# TopSheet.net
KiCad netlist of a schematic drawn in Altium Designer
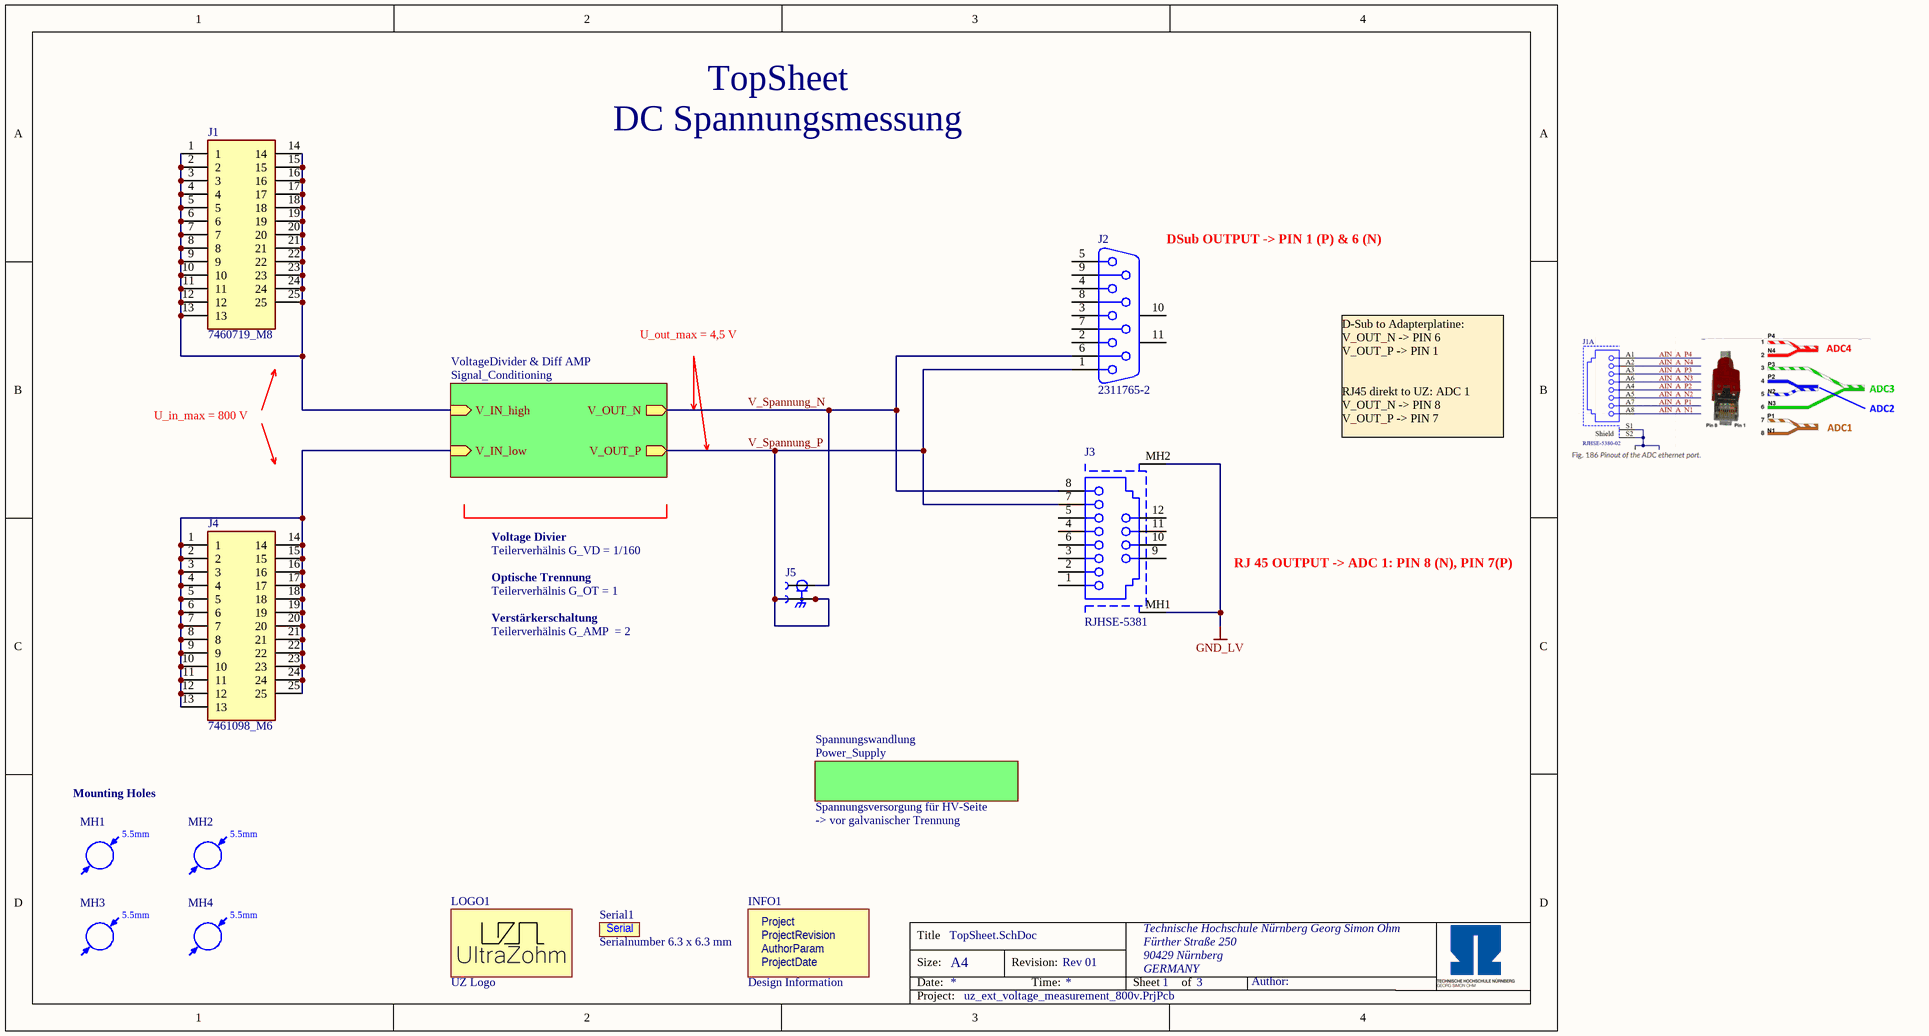
[diagram p0: TopSheet.SchDoc]

(export (version "E")
  (design (tool "Eeschema 10.0.6"))
  (components
    (comp (ref "INFO1")
      (value "Design Information")
      (footprint "Design_info")
      (description "Design InformationS")
      (fields (field (name "MANUFACTURER") "UltraZohm") (field (name "CREATED FROM") "MGremer"))
      (libsource (lib "user") (part "Design_info"))
    )
    (comp (ref "J1")
      (value "7460719_M8")
      (footprint "eigene_lib_alt:7460719")
      (description "Connector")
      (fields
        (field (name "MANUFACTURER_PART_NUMBER") "7460719")
        (field (name "MOUSER PART NUMBER") "710-7460719")
      )
      (libsource (lib "SamacSys") (part "7460719_M8"))
    )
    (comp (ref "J2")
      (value "2311765-2")
      (footprint "2311765-2:2311765-2")
      (description "Connector D-Sub 9 Pin Female")
      (libsource (lib "2311765-2") (part "2311765-2"))
    )
    (comp (ref "J3")
      (value "RJHSE-5381")
      (footprint "eigene_lib_alt:RJHSE-5381")
      (description "Connector Ethernet R/A RJ45 SHIELDED 8 CONT Y/G LEDS")
      (libsource (lib "eigene_lib_alt") (part "RJHSE-5381"))
    )
    (comp (ref "J4")
      (value "7461098_M6")
      (footprint "eigene_lib_alt:7461098")
      (description "Connector")
      (fields
        (field (name "MANUFACTURER_PART_NUMBER") "7461098")
        (field (name "MOUSER PART NUMBER") "710-7461098")
      )
      (libsource (lib "eigene_lib_alt") (part "7461098_M6"))
    )
    (comp (ref "J5")
      (value "BNC5-J-P-GN-ST-TH2D_new")
      (footprint "eigene_lib_alt:BNC5-J-P-GN-ST-TH2D_new")
      (description "BNC Connector")
      (libsource (lib "SamacSys") (part "BNC5-J-P-GN-ST-TH2D_new"))
    )
    (comp (ref "LOGO1")
      (value "UZ Logo")
      (footprint "UZ_Logo_small")
      (fields
        (field (name "MANUFACTURER PART NUMBER") "Logo small")
        (field (name "MANUFACTURER") "UltraZohm")
        (field (name "CREATED") "Jan2021_Liegmann")
        (field (name "CREATED FROM") "MGremer")
      )
      (libsource (lib "user") (part "UZ Logo"))
    )
    (comp (ref "MH1")
      (value "Mounting_Hole_M5")
      (footprint "Mounting_Hole_M5:Mounting Hole (M5)")
      (description "Mounting Hole")
      (libsource (lib "Mounting_Hole_M5") (part "Mounting_Hole_M5"))
    )
    (comp (ref "MH2")
      (value "Mounting_Hole_M5")
      (footprint "Mounting_Hole_M5:Mounting Hole (M5)")
      (description "Mounting Hole")
      (libsource (lib "Mounting_Hole_M5") (part "Mounting_Hole_M5"))
    )
    (comp (ref "MH3")
      (value "Mounting_Hole_M5")
      (footprint "Mounting_Hole_M5:Mounting Hole (M5)")
      (description "Mounting Hole")
      (libsource (lib "Mounting_Hole_M5") (part "Mounting_Hole_M5"))
    )
    (comp (ref "MH4")
      (value "Mounting_Hole_M5")
      (footprint "Mounting_Hole_M5:Mounting Hole (M5)")
      (description "Mounting Hole")
      (libsource (lib "Mounting_Hole_M5") (part "Mounting_Hole_M5"))
    )
    (comp (ref "Serial1")
      (value "Serialnumber 6.3 x 6.3 mm")
      (footprint "SERIAL_6.3X6.3MM")
      (description "Serial Number")
      (fields
        (field (name "MANUFACTURER") "UltraZohm")
        (field (name "CREATED") "2018_09_18_AGeiger")
        (field (name "CREATED FROM") "MGremer")
      )
      (libsource (lib "user") (part "SerialNumber"))
    )
  )
  (nets
    (net (code "1") (name "/V_IN_high") (class "Default")
      (node (ref "J1") (pin "1") (pinfunction "1_1") (pintype "passive"))
      (node (ref "J1") (pin "10") (pinfunction "10_10") (pintype "passive"))
      (node (ref "J1") (pin "11") (pinfunction "11_11") (pintype "passive"))
      (node (ref "J1") (pin "12") (pinfunction "12_12") (pintype "passive"))
      (node (ref "J1") (pin "13") (pinfunction "13_13") (pintype "passive"))
      (node (ref "J1") (pin "14") (pinfunction "14_14") (pintype "passive"))
      (node (ref "J1") (pin "15") (pinfunction "15_15") (pintype "passive"))
      (node (ref "J1") (pin "16") (pinfunction "16_16") (pintype "passive"))
      (node (ref "J1") (pin "17") (pinfunction "17_17") (pintype "passive"))
      (node (ref "J1") (pin "18") (pinfunction "18_18") (pintype "passive"))
      (node (ref "J1") (pin "19") (pinfunction "19_19") (pintype "passive"))
      (node (ref "J1") (pin "2") (pinfunction "2_2") (pintype "passive"))
      (node (ref "J1") (pin "20") (pinfunction "20_20") (pintype "passive"))
      (node (ref "J1") (pin "21") (pinfunction "21_21") (pintype "passive"))
      (node (ref "J1") (pin "22") (pinfunction "22_22") (pintype "passive"))
      (node (ref "J1") (pin "23") (pinfunction "23_23") (pintype "passive"))
      (node (ref "J1") (pin "24") (pinfunction "24_24") (pintype "passive"))
      (node (ref "J1") (pin "25") (pinfunction "25_25") (pintype "passive"))
      (node (ref "J1") (pin "3") (pinfunction "3_3") (pintype "passive"))
      (node (ref "J1") (pin "4") (pinfunction "4_4") (pintype "passive"))
      (node (ref "J1") (pin "5") (pinfunction "5_5") (pintype "passive"))
      (node (ref "J1") (pin "6") (pinfunction "6_6") (pintype "passive"))
      (node (ref "J1") (pin "7") (pinfunction "7_7") (pintype "passive"))
      (node (ref "J1") (pin "8") (pinfunction "8_8") (pintype "passive"))
      (node (ref "J1") (pin "9") (pinfunction "9_9") (pintype "passive"))
    )
    (net (code "2") (name "/V_IN_low") (class "Default")
      (node (ref "J4") (pin "1") (pinfunction "1_1") (pintype "passive"))
      (node (ref "J4") (pin "10") (pinfunction "10_10") (pintype "passive"))
      (node (ref "J4") (pin "11") (pinfunction "11_11") (pintype "passive"))
      (node (ref "J4") (pin "12") (pinfunction "12_12") (pintype "passive"))
      (node (ref "J4") (pin "13") (pinfunction "13_13") (pintype "passive"))
      (node (ref "J4") (pin "14") (pinfunction "14_14") (pintype "passive"))
      (node (ref "J4") (pin "15") (pinfunction "15_15") (pintype "passive"))
      (node (ref "J4") (pin "16") (pinfunction "16_16") (pintype "passive"))
      (node (ref "J4") (pin "17") (pinfunction "17_17") (pintype "passive"))
      (node (ref "J4") (pin "18") (pinfunction "18_18") (pintype "passive"))
      (node (ref "J4") (pin "19") (pinfunction "19_19") (pintype "passive"))
      (node (ref "J4") (pin "2") (pinfunction "2_2") (pintype "passive"))
      (node (ref "J4") (pin "20") (pinfunction "20_20") (pintype "passive"))
      (node (ref "J4") (pin "21") (pinfunction "21_21") (pintype "passive"))
      (node (ref "J4") (pin "22") (pinfunction "22_22") (pintype "passive"))
      (node (ref "J4") (pin "23") (pinfunction "23_23") (pintype "passive"))
      (node (ref "J4") (pin "24") (pinfunction "24_24") (pintype "passive"))
      (node (ref "J4") (pin "25") (pinfunction "25_25") (pintype "passive"))
      (node (ref "J4") (pin "3") (pinfunction "3_3") (pintype "passive"))
      (node (ref "J4") (pin "4") (pinfunction "4_4") (pintype "passive"))
      (node (ref "J4") (pin "5") (pinfunction "5_5") (pintype "passive"))
      (node (ref "J4") (pin "6") (pinfunction "6_6") (pintype "passive"))
      (node (ref "J4") (pin "7") (pinfunction "7_7") (pintype "passive"))
      (node (ref "J4") (pin "8") (pinfunction "8_8") (pintype "passive"))
      (node (ref "J4") (pin "9") (pinfunction "9_9") (pintype "passive"))
    )
    (net (code "3") (name "/V_Spannung_N") (class "Default")
      (node (ref "J2") (pin "6") (pinfunction "6_6") (pintype "passive"))
      (node (ref "J3") (pin "8") (pinfunction "8_8") (pintype "passive"))
      (node (ref "J5") (pin "1") (pinfunction "1_1") (pintype "passive"))
    )
    (net (code "4") (name "/V_Spannung_P") (class "Default")
      (node (ref "J2") (pin "1") (pinfunction "1_1") (pintype "passive"))
      (node (ref "J3") (pin "7") (pinfunction "7_7") (pintype "passive"))
      (node (ref "J5") (pin "S_1") (pinfunction "2_S_1") (pintype "passive"))
      (node (ref "J5") (pin "S_2") (pinfunction "2_S_2") (pintype "passive"))
      (node (ref "J5") (pin "S_3") (pinfunction "2_S_3") (pintype "passive"))
    )
    (net (code "5") (name "GND_LV") (class "Default")
      (node (ref "J3") (pin "MH1") (pinfunction "Shell_MH1") (pintype "passive"))
      (node (ref "J3") (pin "MH2") (pinfunction "Shell_MH2") (pintype "passive"))
    )
    (net (code "6") (name "unconnected-(J2-MH1-Pad10)") (class "Default")
      (node (ref "J2") (pin "10") (pinfunction "MH1_10") (pintype "passive"))
    )
    (net (code "7") (name "unconnected-(J2-MH2-Pad11)") (class "Default")
      (node (ref "J2") (pin "11") (pinfunction "MH2_11") (pintype "passive"))
    )
    (net (code "8") (name "unconnected-(J2-Pad2)") (class "Default")
      (node (ref "J2") (pin "2") (pinfunction "2_2") (pintype "passive"))
    )
    (net (code "9") (name "unconnected-(J2-Pad3)") (class "Default")
      (node (ref "J2") (pin "3") (pinfunction "3_3") (pintype "passive"))
    )
    (net (code "10") (name "unconnected-(J2-Pad4)") (class "Default")
      (node (ref "J2") (pin "4") (pinfunction "4_4") (pintype "passive"))
    )
    (net (code "11") (name "unconnected-(J2-Pad5)") (class "Default")
      (node (ref "J2") (pin "5") (pinfunction "5_5") (pintype "passive"))
    )
    (net (code "12") (name "unconnected-(J2-Pad7)") (class "Default")
      (node (ref "J2") (pin "7") (pinfunction "7_7") (pintype "passive"))
    )
    (net (code "13") (name "unconnected-(J2-Pad8)") (class "Default")
      (node (ref "J2") (pin "8") (pinfunction "8_8") (pintype "passive"))
    )
    (net (code "14") (name "unconnected-(J2-Pad9)") (class "Default")
      (node (ref "J2") (pin "9") (pinfunction "9_9") (pintype "passive"))
    )
    (net (code "15") (name "unconnected-(J3-8-Pad9)") (class "Default")
      (node (ref "J3") (pin "9") (pinfunction "8_9") (pintype "passive"))
    )
    (net (code "16") (name "unconnected-(J3-8-Pad10)") (class "Default")
      (node (ref "J3") (pin "10") (pinfunction "8_10") (pintype "passive"))
    )
    (net (code "17") (name "unconnected-(J3-8-Pad11)") (class "Default")
      (node (ref "J3") (pin "11") (pinfunction "8_11") (pintype "passive"))
    )
    (net (code "18") (name "unconnected-(J3-8-Pad12)") (class "Default")
      (node (ref "J3") (pin "12") (pinfunction "8_12") (pintype "passive"))
    )
    (net (code "19") (name "unconnected-(J3-Pad1)") (class "Default")
      (node (ref "J3") (pin "1") (pinfunction "1_1") (pintype "passive"))
    )
    (net (code "20") (name "unconnected-(J3-Pad2)") (class "Default")
      (node (ref "J3") (pin "2") (pinfunction "2_2") (pintype "passive"))
    )
    (net (code "21") (name "unconnected-(J3-Pad3)") (class "Default")
      (node (ref "J3") (pin "3") (pinfunction "3_3") (pintype "passive"))
    )
    (net (code "22") (name "unconnected-(J3-Pad4)") (class "Default")
      (node (ref "J3") (pin "4") (pinfunction "4_4") (pintype "passive"))
    )
    (net (code "23") (name "unconnected-(J3-Pad5)") (class "Default")
      (node (ref "J3") (pin "5") (pinfunction "5_5") (pintype "passive"))
    )
    (net (code "24") (name "unconnected-(J3-Pad6)") (class "Default")
      (node (ref "J3") (pin "6") (pinfunction "6_6") (pintype "passive"))
    )
  )
)
